# Proyecto_etapa_1_y_2.net
KiCad netlist of a schematic drawn in EAGLE
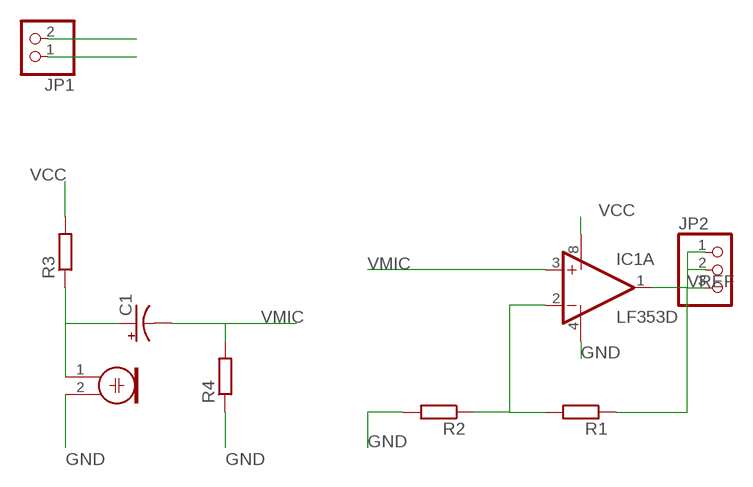
[diagram p0: schematic, sheet 1]

(export (version "E")
  (design (tool "Eeschema 10.0.6"))
  (components
    (comp (ref "C1")
      (value "CPOL-USC/6032-28R")
      (footprint "eagle-import:C_6032-28R")
      (libsource (lib "eagle-import") (part "CPOL-USC/6032-28R"))
    )
    (comp (ref "IC1")
      (value "LF353D")
      (footprint "eagle-import:SO08")
      (libsource (lib "eagle-import") (part "LF353D"))
    )
    (comp (ref "JP1")
      (value "PINHD-1X2")
      (footprint "eagle-import:1X02")
      (libsource (lib "eagle-import") (part "PINHD-1X2"))
    )
    (comp (ref "JP2")
      (value "PINHD-1X3")
      (footprint "eagle-import:1X03")
      (libsource (lib "eagle-import") (part "PINHD-1X3"))
    )
    (comp (ref "M1")
      (value "ELECTRET_MICROPHON-WM-62PC/62PK")
      (footprint "eagle-import:WM-62PC_62PK")
      (libsource (lib "eagle-import") (part "ELECTRET_MICROPHON-WM-62PC/62PK"))
    )
    (comp (ref "R1")
      (value "R-EU_R0603")
      (footprint "eagle-import:R0603")
      (libsource (lib "eagle-import") (part "R-EU_R0603"))
    )
    (comp (ref "R2")
      (value "R-EU_R0603")
      (footprint "eagle-import:R0603")
      (libsource (lib "eagle-import") (part "R-EU_R0603"))
    )
    (comp (ref "R3")
      (value "R-EU_R0603")
      (footprint "eagle-import:R0603")
      (libsource (lib "eagle-import") (part "R-EU_R0603"))
    )
    (comp (ref "R4")
      (value "R-EU_R0603")
      (footprint "eagle-import:R0603")
      (libsource (lib "eagle-import") (part "R-EU_R0603"))
    )
  )
  (nets
    (net (code "1") (name "/GND") (class "Default")
      (node (ref "IC1") (pin "4") (pinfunction "V-_4") (pintype "power_in"))
      (node (ref "JP1") (pin "2") (pinfunction "2_2") (pintype "passive"))
      (node (ref "M1") (pin "2") (pinfunction "2_2") (pintype "passive"))
      (node (ref "R2") (pin "2") (pinfunction "2_2") (pintype "passive"))
      (node (ref "R4") (pin "1") (pinfunction "1_1") (pintype "passive"))
    )
    (net (code "2") (name "/VCC") (class "Default")
      (node (ref "IC1") (pin "8") (pinfunction "V+_8") (pintype "power_in"))
      (node (ref "JP1") (pin "1") (pinfunction "1_1") (pintype "passive"))
      (node (ref "R3") (pin "2") (pinfunction "2_2") (pintype "passive"))
    )
    (net (code "3") (name "/VMIC") (class "Default")
      (node (ref "C1") (pin "-") (pinfunction "-_-") (pintype "passive"))
      (node (ref "IC1") (pin "3") (pinfunction "+IN_3") (pintype "input"))
      (node (ref "R4") (pin "2") (pinfunction "2_2") (pintype "passive"))
    )
    (net (code "4") (name "/VREF") (class "Default")
      (node (ref "IC1") (pin "1") (pinfunction "OUT_1") (pintype "output"))
      (node (ref "JP2") (pin "1") (pinfunction "1_1") (pintype "passive"))
      (node (ref "JP2") (pin "2") (pinfunction "2_2") (pintype "passive"))
      (node (ref "JP2") (pin "3") (pinfunction "3_3") (pintype "passive"))
      (node (ref "R1") (pin "1") (pinfunction "1_1") (pintype "passive"))
    )
    (net (code "5") (name "Net-(C1-Pad+)") (class "Default")
      (node (ref "C1") (pin "+") (pinfunction "+_+") (pintype "passive"))
      (node (ref "M1") (pin "1") (pinfunction "1_1") (pintype "passive"))
      (node (ref "R3") (pin "1") (pinfunction "1_1") (pintype "passive"))
    )
    (net (code "6") (name "Net-(IC1A--IN)") (class "Default")
      (node (ref "IC1") (pin "2") (pinfunction "-IN_2") (pintype "input"))
      (node (ref "R1") (pin "2") (pinfunction "2_2") (pintype "passive"))
      (node (ref "R2") (pin "1") (pinfunction "1_1") (pintype "passive"))
    )
  )
)
